# Sheet1.net
KiCad netlist of a schematic drawn in Altium Designer
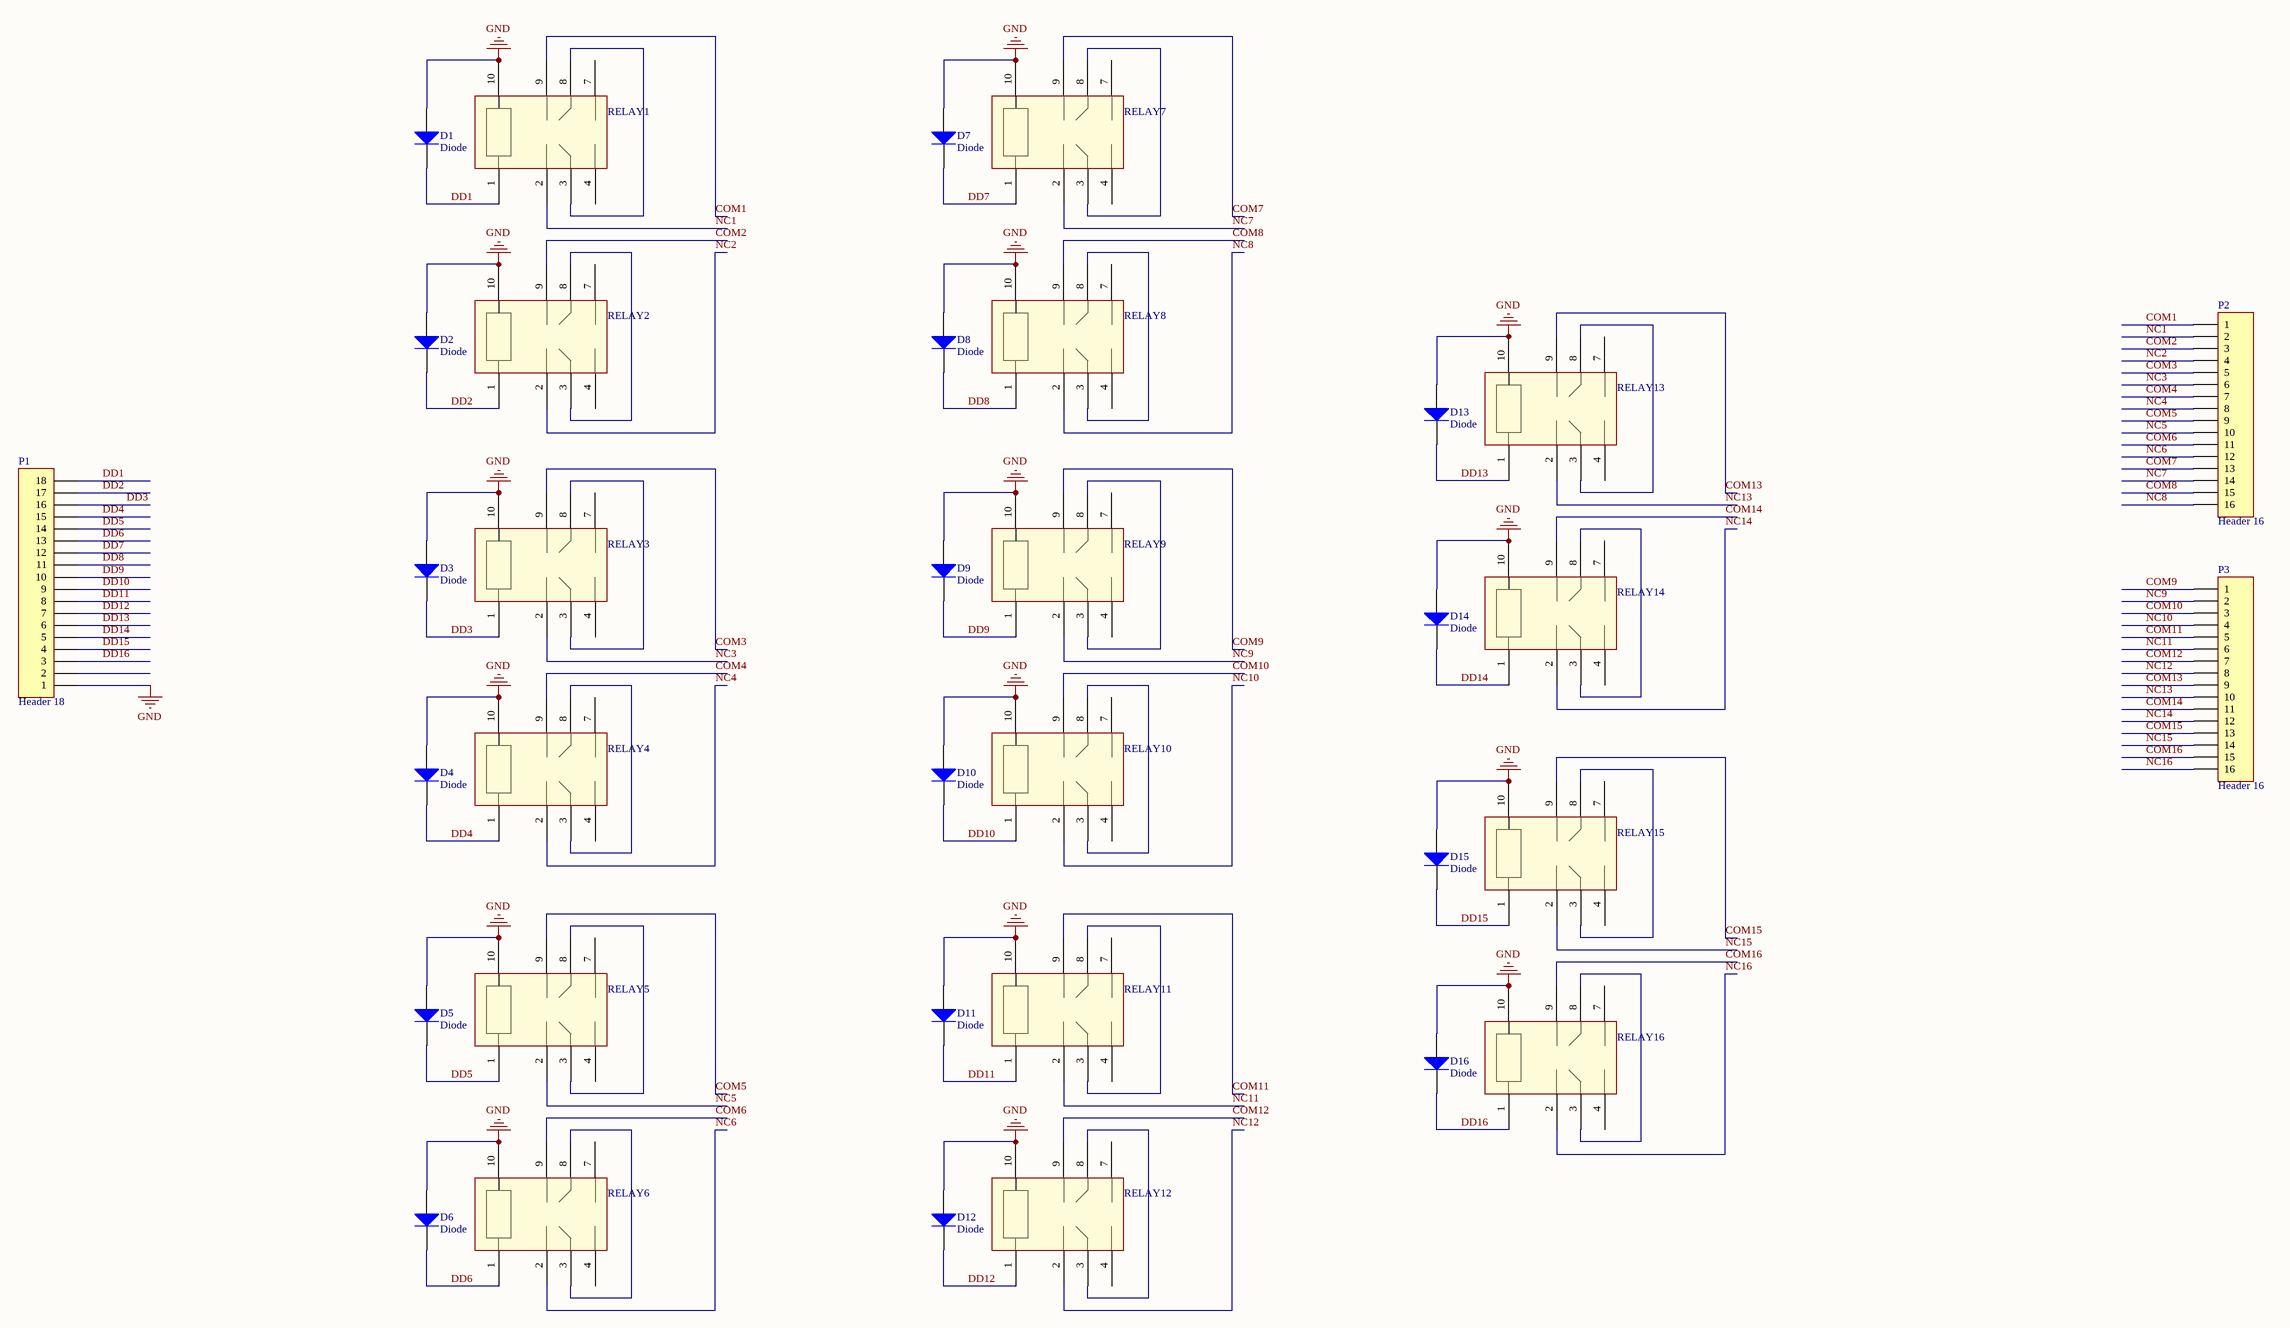
[diagram p0: Sheet1.SchDoc]

(export (version "E")
  (design (tool "Eeschema 10.0.6"))
  (components
    (comp (ref "D1")
      (value "Diode")
      (footprint "SMC")
      (description "Default Diode")
      (fields (field (name "PUBLISHER") "Altium Limited"))
      (libsource (lib "Miscellaneous Devices") (part "Diode"))
    )
    (comp (ref "D2")
      (value "Diode")
      (footprint "SMC")
      (description "Default Diode")
      (fields (field (name "PUBLISHER") "Altium Limited"))
      (libsource (lib "Miscellaneous Devices") (part "Diode"))
    )
    (comp (ref "D3")
      (value "Diode")
      (footprint "SMC")
      (description "Default Diode")
      (fields (field (name "PUBLISHER") "Altium Limited"))
      (libsource (lib "Miscellaneous Devices") (part "Diode"))
    )
    (comp (ref "D4")
      (value "Diode")
      (footprint "SMC")
      (description "Default Diode")
      (fields (field (name "PUBLISHER") "Altium Limited"))
      (libsource (lib "Miscellaneous Devices") (part "Diode"))
    )
    (comp (ref "D5")
      (value "Diode")
      (footprint "SMC")
      (description "Default Diode")
      (fields (field (name "PUBLISHER") "Altium Limited"))
      (libsource (lib "Miscellaneous Devices") (part "Diode"))
    )
    (comp (ref "D6")
      (value "Diode")
      (footprint "SMC")
      (description "Default Diode")
      (fields (field (name "PUBLISHER") "Altium Limited"))
      (libsource (lib "Miscellaneous Devices") (part "Diode"))
    )
    (comp (ref "D7")
      (value "Diode")
      (footprint "SMC")
      (description "Default Diode")
      (fields (field (name "PUBLISHER") "Altium Limited"))
      (libsource (lib "Miscellaneous Devices") (part "Diode"))
    )
    (comp (ref "D8")
      (value "Diode")
      (footprint "SMC")
      (description "Default Diode")
      (fields (field (name "PUBLISHER") "Altium Limited"))
      (libsource (lib "Miscellaneous Devices") (part "Diode"))
    )
    (comp (ref "D9")
      (value "Diode")
      (footprint "SMC")
      (description "Default Diode")
      (fields (field (name "PUBLISHER") "Altium Limited"))
      (libsource (lib "Miscellaneous Devices") (part "Diode"))
    )
    (comp (ref "D10")
      (value "Diode")
      (footprint "SMC")
      (description "Default Diode")
      (fields (field (name "PUBLISHER") "Altium Limited"))
      (libsource (lib "Miscellaneous Devices") (part "Diode"))
    )
    (comp (ref "D11")
      (value "Diode")
      (footprint "SMC")
      (description "Default Diode")
      (fields (field (name "PUBLISHER") "Altium Limited"))
      (libsource (lib "Miscellaneous Devices") (part "Diode"))
    )
    (comp (ref "D12")
      (value "Diode")
      (footprint "SMC")
      (description "Default Diode")
      (fields (field (name "PUBLISHER") "Altium Limited"))
      (libsource (lib "Miscellaneous Devices") (part "Diode"))
    )
    (comp (ref "D13")
      (value "Diode")
      (footprint "SMC")
      (description "Default Diode")
      (fields (field (name "PUBLISHER") "Altium Limited"))
      (libsource (lib "Miscellaneous Devices") (part "Diode"))
    )
    (comp (ref "D14")
      (value "Diode")
      (footprint "SMC")
      (description "Default Diode")
      (fields (field (name "PUBLISHER") "Altium Limited"))
      (libsource (lib "Miscellaneous Devices") (part "Diode"))
    )
    (comp (ref "D15")
      (value "Diode")
      (footprint "SMC")
      (description "Default Diode")
      (fields (field (name "PUBLISHER") "Altium Limited"))
      (libsource (lib "Miscellaneous Devices") (part "Diode"))
    )
    (comp (ref "D16")
      (value "Diode")
      (footprint "SMC")
      (description "Default Diode")
      (fields (field (name "PUBLISHER") "Altium Limited"))
      (libsource (lib "Miscellaneous Devices") (part "Diode"))
    )
    (comp (ref "P1")
      (value "Header 18")
      (footprint "CON 18")
      (description "Header, 18-Pin")
      (fields (field (name "PUBLISHER") "Altium Limited"))
      (libsource (lib "Miscellaneous Connectors") (part "Header 18"))
    )
    (comp (ref "P2")
      (value "Header 16")
      (footprint "CON 16")
      (description "Header, 16-Pin")
      (fields (field (name "PUBLISHER") "Altium Limited"))
      (libsource (lib "Miscellaneous Connectors") (part "Header 16"))
    )
    (comp (ref "P3")
      (value "Header 16")
      (footprint "CON 16")
      (description "Header, 16-Pin")
      (fields (field (name "PUBLISHER") "Altium Limited"))
      (libsource (lib "Miscellaneous Connectors") (part "Header 16"))
    )
    (comp (ref "RELAY1")
      (value "OMRON RELAY")
      (footprint "G6H-2")
      (libsource (lib "dung_maker_2018") (part "OMRON G6H-2"))
    )
    (comp (ref "RELAY2")
      (value "OMRON RELAY")
      (footprint "G6H-2")
      (libsource (lib "dung_maker_2018") (part "OMRON G6H-2"))
    )
    (comp (ref "RELAY3")
      (value "OMRON RELAY")
      (footprint "G6H-2")
      (libsource (lib "dung_maker_2018") (part "OMRON G6H-2"))
    )
    (comp (ref "RELAY4")
      (value "OMRON RELAY")
      (footprint "G6H-2")
      (libsource (lib "dung_maker_2018") (part "OMRON G6H-2"))
    )
    (comp (ref "RELAY5")
      (value "OMRON RELAY")
      (footprint "G6H-2")
      (libsource (lib "dung_maker_2018") (part "OMRON G6H-2"))
    )
    (comp (ref "RELAY6")
      (value "OMRON RELAY")
      (footprint "G6H-2")
      (libsource (lib "dung_maker_2018") (part "OMRON G6H-2"))
    )
    (comp (ref "RELAY7")
      (value "OMRON RELAY")
      (footprint "G6H-2")
      (libsource (lib "dung_maker_2018") (part "OMRON G6H-2"))
    )
    (comp (ref "RELAY8")
      (value "OMRON RELAY")
      (footprint "G6H-2")
      (libsource (lib "dung_maker_2018") (part "OMRON G6H-2"))
    )
    (comp (ref "RELAY9")
      (value "OMRON RELAY")
      (footprint "G6H-2")
      (libsource (lib "dung_maker_2018") (part "OMRON G6H-2"))
    )
    (comp (ref "RELAY10")
      (value "OMRON RELAY")
      (footprint "G6H-2")
      (libsource (lib "dung_maker_2018") (part "OMRON G6H-2"))
    )
    (comp (ref "RELAY11")
      (value "OMRON RELAY")
      (footprint "G6H-2")
      (libsource (lib "dung_maker_2018") (part "OMRON G6H-2"))
    )
    (comp (ref "RELAY12")
      (value "OMRON RELAY")
      (footprint "G6H-2")
      (libsource (lib "dung_maker_2018") (part "OMRON G6H-2"))
    )
    (comp (ref "RELAY13")
      (value "OMRON RELAY")
      (footprint "G6H-2")
      (libsource (lib "dung_maker_2018") (part "OMRON G6H-2"))
    )
    (comp (ref "RELAY14")
      (value "OMRON RELAY")
      (footprint "G6H-2")
      (libsource (lib "dung_maker_2018") (part "OMRON G6H-2"))
    )
    (comp (ref "RELAY15")
      (value "OMRON RELAY")
      (footprint "G6H-2")
      (libsource (lib "dung_maker_2018") (part "OMRON G6H-2"))
    )
    (comp (ref "RELAY16")
      (value "OMRON RELAY")
      (footprint "G6H-2")
      (libsource (lib "dung_maker_2018") (part "OMRON G6H-2"))
    )
  )
  (nets
    (net (code "1") (name "/COM1") (class "Default")
      (node (ref "P2") (pin "1") (pinfunction "1_1") (pintype "passive"))
      (node (ref "RELAY1") (pin "9") (pinfunction "9_9") (pintype "passive"))
    )
    (net (code "2") (name "/COM2") (class "Default")
      (node (ref "P2") (pin "3") (pinfunction "3_3") (pintype "passive"))
      (node (ref "RELAY2") (pin "9") (pinfunction "9_9") (pintype "passive"))
    )
    (net (code "3") (name "/COM3") (class "Default")
      (node (ref "P2") (pin "5") (pinfunction "5_5") (pintype "passive"))
      (node (ref "RELAY3") (pin "9") (pinfunction "9_9") (pintype "passive"))
    )
    (net (code "4") (name "/COM4") (class "Default")
      (node (ref "P2") (pin "7") (pinfunction "7_7") (pintype "passive"))
      (node (ref "RELAY4") (pin "9") (pinfunction "9_9") (pintype "passive"))
    )
    (net (code "5") (name "/COM5") (class "Default")
      (node (ref "P2") (pin "9") (pinfunction "9_9") (pintype "passive"))
      (node (ref "RELAY5") (pin "9") (pinfunction "9_9") (pintype "passive"))
    )
    (net (code "6") (name "/COM6") (class "Default")
      (node (ref "P2") (pin "11") (pinfunction "11_11") (pintype "passive"))
      (node (ref "RELAY6") (pin "9") (pinfunction "9_9") (pintype "passive"))
    )
    (net (code "7") (name "/COM7") (class "Default")
      (node (ref "P2") (pin "13") (pinfunction "13_13") (pintype "passive"))
      (node (ref "RELAY7") (pin "9") (pinfunction "9_9") (pintype "passive"))
    )
    (net (code "8") (name "/COM8") (class "Default")
      (node (ref "P2") (pin "15") (pinfunction "15_15") (pintype "passive"))
      (node (ref "RELAY8") (pin "9") (pinfunction "9_9") (pintype "passive"))
    )
    (net (code "9") (name "/COM9") (class "Default")
      (node (ref "P3") (pin "1") (pinfunction "1_1") (pintype "passive"))
      (node (ref "RELAY9") (pin "9") (pinfunction "9_9") (pintype "passive"))
    )
    (net (code "10") (name "/COM10") (class "Default")
      (node (ref "P3") (pin "3") (pinfunction "3_3") (pintype "passive"))
      (node (ref "RELAY10") (pin "9") (pinfunction "9_9") (pintype "passive"))
    )
    (net (code "11") (name "/COM11") (class "Default")
      (node (ref "P3") (pin "5") (pinfunction "5_5") (pintype "passive"))
      (node (ref "RELAY11") (pin "9") (pinfunction "9_9") (pintype "passive"))
    )
    (net (code "12") (name "/COM12") (class "Default")
      (node (ref "P3") (pin "7") (pinfunction "7_7") (pintype "passive"))
      (node (ref "RELAY12") (pin "9") (pinfunction "9_9") (pintype "passive"))
    )
    (net (code "13") (name "/COM13") (class "Default")
      (node (ref "P3") (pin "9") (pinfunction "9_9") (pintype "passive"))
      (node (ref "RELAY13") (pin "9") (pinfunction "9_9") (pintype "passive"))
    )
    (net (code "14") (name "/COM14") (class "Default")
      (node (ref "P3") (pin "11") (pinfunction "11_11") (pintype "passive"))
      (node (ref "RELAY14") (pin "9") (pinfunction "9_9") (pintype "passive"))
    )
    (net (code "15") (name "/COM15") (class "Default")
      (node (ref "P3") (pin "13") (pinfunction "13_13") (pintype "passive"))
      (node (ref "RELAY15") (pin "9") (pinfunction "9_9") (pintype "passive"))
    )
    (net (code "16") (name "/COM16") (class "Default")
      (node (ref "P3") (pin "15") (pinfunction "15_15") (pintype "passive"))
      (node (ref "RELAY16") (pin "9") (pinfunction "9_9") (pintype "passive"))
    )
    (net (code "17") (name "/DD1") (class "Default")
      (node (ref "D1") (pin "2") (pinfunction "K_2") (pintype "passive"))
      (node (ref "P1") (pin "18") (pinfunction "18_18") (pintype "passive"))
      (node (ref "RELAY1") (pin "1") (pinfunction "1_1") (pintype "passive"))
    )
    (net (code "18") (name "/DD2") (class "Default")
      (node (ref "D2") (pin "2") (pinfunction "K_2") (pintype "passive"))
      (node (ref "P1") (pin "17") (pinfunction "17_17") (pintype "passive"))
      (node (ref "RELAY2") (pin "1") (pinfunction "1_1") (pintype "passive"))
    )
    (net (code "19") (name "/DD3") (class "Default")
      (node (ref "D3") (pin "2") (pinfunction "K_2") (pintype "passive"))
      (node (ref "P1") (pin "16") (pinfunction "16_16") (pintype "passive"))
      (node (ref "RELAY3") (pin "1") (pinfunction "1_1") (pintype "passive"))
    )
    (net (code "20") (name "/DD4") (class "Default")
      (node (ref "D4") (pin "2") (pinfunction "K_2") (pintype "passive"))
      (node (ref "P1") (pin "15") (pinfunction "15_15") (pintype "passive"))
      (node (ref "RELAY4") (pin "1") (pinfunction "1_1") (pintype "passive"))
    )
    (net (code "21") (name "/DD5") (class "Default")
      (node (ref "D5") (pin "2") (pinfunction "K_2") (pintype "passive"))
      (node (ref "P1") (pin "14") (pinfunction "14_14") (pintype "passive"))
      (node (ref "RELAY5") (pin "1") (pinfunction "1_1") (pintype "passive"))
    )
    (net (code "22") (name "/DD6") (class "Default")
      (node (ref "D6") (pin "2") (pinfunction "K_2") (pintype "passive"))
      (node (ref "P1") (pin "13") (pinfunction "13_13") (pintype "passive"))
      (node (ref "RELAY6") (pin "1") (pinfunction "1_1") (pintype "passive"))
    )
    (net (code "23") (name "/DD7") (class "Default")
      (node (ref "D7") (pin "2") (pinfunction "K_2") (pintype "passive"))
      (node (ref "P1") (pin "12") (pinfunction "12_12") (pintype "passive"))
      (node (ref "RELAY7") (pin "1") (pinfunction "1_1") (pintype "passive"))
    )
    (net (code "24") (name "/DD8") (class "Default")
      (node (ref "D8") (pin "2") (pinfunction "K_2") (pintype "passive"))
      (node (ref "P1") (pin "11") (pinfunction "11_11") (pintype "passive"))
      (node (ref "RELAY8") (pin "1") (pinfunction "1_1") (pintype "passive"))
    )
    (net (code "25") (name "/DD9") (class "Default")
      (node (ref "D9") (pin "2") (pinfunction "K_2") (pintype "passive"))
      (node (ref "P1") (pin "10") (pinfunction "10_10") (pintype "passive"))
      (node (ref "RELAY9") (pin "1") (pinfunction "1_1") (pintype "passive"))
    )
    (net (code "26") (name "/DD10") (class "Default")
      (node (ref "D10") (pin "2") (pinfunction "K_2") (pintype "passive"))
      (node (ref "P1") (pin "9") (pinfunction "9_9") (pintype "passive"))
      (node (ref "RELAY10") (pin "1") (pinfunction "1_1") (pintype "passive"))
    )
    (net (code "27") (name "/DD11") (class "Default")
      (node (ref "D11") (pin "2") (pinfunction "K_2") (pintype "passive"))
      (node (ref "P1") (pin "8") (pinfunction "8_8") (pintype "passive"))
      (node (ref "RELAY11") (pin "1") (pinfunction "1_1") (pintype "passive"))
    )
    (net (code "28") (name "/DD12") (class "Default")
      (node (ref "D12") (pin "2") (pinfunction "K_2") (pintype "passive"))
      (node (ref "P1") (pin "7") (pinfunction "7_7") (pintype "passive"))
      (node (ref "RELAY12") (pin "1") (pinfunction "1_1") (pintype "passive"))
    )
    (net (code "29") (name "/DD13") (class "Default")
      (node (ref "D13") (pin "2") (pinfunction "K_2") (pintype "passive"))
      (node (ref "P1") (pin "6") (pinfunction "6_6") (pintype "passive"))
      (node (ref "RELAY13") (pin "1") (pinfunction "1_1") (pintype "passive"))
    )
    (net (code "30") (name "/DD14") (class "Default")
      (node (ref "D14") (pin "2") (pinfunction "K_2") (pintype "passive"))
      (node (ref "P1") (pin "5") (pinfunction "5_5") (pintype "passive"))
      (node (ref "RELAY14") (pin "1") (pinfunction "1_1") (pintype "passive"))
    )
    (net (code "31") (name "/DD15") (class "Default")
      (node (ref "D15") (pin "2") (pinfunction "K_2") (pintype "passive"))
      (node (ref "P1") (pin "4") (pinfunction "4_4") (pintype "passive"))
      (node (ref "RELAY15") (pin "1") (pinfunction "1_1") (pintype "passive"))
    )
    (net (code "32") (name "/DD16") (class "Default")
      (node (ref "D16") (pin "2") (pinfunction "K_2") (pintype "passive"))
      (node (ref "P1") (pin "3") (pinfunction "3_3") (pintype "passive"))
      (node (ref "RELAY16") (pin "1") (pinfunction "1_1") (pintype "passive"))
    )
    (net (code "33") (name "/NC1") (class "Default")
      (node (ref "P2") (pin "2") (pinfunction "2_2") (pintype "passive"))
      (node (ref "RELAY1") (pin "2") (pinfunction "2_2") (pintype "passive"))
    )
    (net (code "34") (name "/NC2") (class "Default")
      (node (ref "P2") (pin "4") (pinfunction "4_4") (pintype "passive"))
      (node (ref "RELAY2") (pin "2") (pinfunction "2_2") (pintype "passive"))
    )
    (net (code "35") (name "/NC3") (class "Default")
      (node (ref "P2") (pin "6") (pinfunction "6_6") (pintype "passive"))
      (node (ref "RELAY3") (pin "2") (pinfunction "2_2") (pintype "passive"))
    )
    (net (code "36") (name "/NC4") (class "Default")
      (node (ref "P2") (pin "8") (pinfunction "8_8") (pintype "passive"))
      (node (ref "RELAY4") (pin "2") (pinfunction "2_2") (pintype "passive"))
    )
    (net (code "37") (name "/NC5") (class "Default")
      (node (ref "P2") (pin "10") (pinfunction "10_10") (pintype "passive"))
      (node (ref "RELAY5") (pin "2") (pinfunction "2_2") (pintype "passive"))
    )
    (net (code "38") (name "/NC6") (class "Default")
      (node (ref "P2") (pin "12") (pinfunction "12_12") (pintype "passive"))
      (node (ref "RELAY6") (pin "2") (pinfunction "2_2") (pintype "passive"))
    )
    (net (code "39") (name "/NC7") (class "Default")
      (node (ref "P2") (pin "14") (pinfunction "14_14") (pintype "passive"))
      (node (ref "RELAY7") (pin "2") (pinfunction "2_2") (pintype "passive"))
    )
    (net (code "40") (name "/NC8") (class "Default")
      (node (ref "P2") (pin "16") (pinfunction "16_16") (pintype "passive"))
      (node (ref "RELAY8") (pin "2") (pinfunction "2_2") (pintype "passive"))
    )
    (net (code "41") (name "/NC9") (class "Default")
      (node (ref "P3") (pin "2") (pinfunction "2_2") (pintype "passive"))
      (node (ref "RELAY9") (pin "2") (pinfunction "2_2") (pintype "passive"))
    )
    (net (code "42") (name "/NC10") (class "Default")
      (node (ref "P3") (pin "4") (pinfunction "4_4") (pintype "passive"))
      (node (ref "RELAY10") (pin "2") (pinfunction "2_2") (pintype "passive"))
    )
    (net (code "43") (name "/NC11") (class "Default")
      (node (ref "P3") (pin "6") (pinfunction "6_6") (pintype "passive"))
      (node (ref "RELAY11") (pin "2") (pinfunction "2_2") (pintype "passive"))
    )
    (net (code "44") (name "/NC12") (class "Default")
      (node (ref "P3") (pin "8") (pinfunction "8_8") (pintype "passive"))
      (node (ref "RELAY12") (pin "2") (pinfunction "2_2") (pintype "passive"))
    )
    (net (code "45") (name "/NC13") (class "Default")
      (node (ref "P3") (pin "10") (pinfunction "10_10") (pintype "passive"))
      (node (ref "RELAY13") (pin "2") (pinfunction "2_2") (pintype "passive"))
    )
    (net (code "46") (name "/NC14") (class "Default")
      (node (ref "P3") (pin "12") (pinfunction "12_12") (pintype "passive"))
      (node (ref "RELAY14") (pin "2") (pinfunction "2_2") (pintype "passive"))
    )
    (net (code "47") (name "/NC15") (class "Default")
      (node (ref "P3") (pin "14") (pinfunction "14_14") (pintype "passive"))
      (node (ref "RELAY15") (pin "2") (pinfunction "2_2") (pintype "passive"))
    )
    (net (code "48") (name "/NC16") (class "Default")
      (node (ref "P3") (pin "16") (pinfunction "16_16") (pintype "passive"))
      (node (ref "RELAY16") (pin "2") (pinfunction "2_2") (pintype "passive"))
    )
    (net (code "49") (name "GND") (class "Default")
      (node (ref "D1") (pin "1") (pinfunction "A_1") (pintype "passive"))
      (node (ref "D10") (pin "1") (pinfunction "A_1") (pintype "passive"))
      (node (ref "D11") (pin "1") (pinfunction "A_1") (pintype "passive"))
      (node (ref "D12") (pin "1") (pinfunction "A_1") (pintype "passive"))
      (node (ref "D13") (pin "1") (pinfunction "A_1") (pintype "passive"))
      (node (ref "D14") (pin "1") (pinfunction "A_1") (pintype "passive"))
      (node (ref "D15") (pin "1") (pinfunction "A_1") (pintype "passive"))
      (node (ref "D16") (pin "1") (pinfunction "A_1") (pintype "passive"))
      (node (ref "D2") (pin "1") (pinfunction "A_1") (pintype "passive"))
      (node (ref "D3") (pin "1") (pinfunction "A_1") (pintype "passive"))
      (node (ref "D4") (pin "1") (pinfunction "A_1") (pintype "passive"))
      (node (ref "D5") (pin "1") (pinfunction "A_1") (pintype "passive"))
      (node (ref "D6") (pin "1") (pinfunction "A_1") (pintype "passive"))
      (node (ref "D7") (pin "1") (pinfunction "A_1") (pintype "passive"))
      (node (ref "D8") (pin "1") (pinfunction "A_1") (pintype "passive"))
      (node (ref "D9") (pin "1") (pinfunction "A_1") (pintype "passive"))
      (node (ref "P1") (pin "1") (pinfunction "1_1") (pintype "passive"))
      (node (ref "RELAY1") (pin "10") (pinfunction "10_10") (pintype "passive"))
      (node (ref "RELAY10") (pin "10") (pinfunction "10_10") (pintype "passive"))
      (node (ref "RELAY11") (pin "10") (pinfunction "10_10") (pintype "passive"))
      (node (ref "RELAY12") (pin "10") (pinfunction "10_10") (pintype "passive"))
      (node (ref "RELAY13") (pin "10") (pinfunction "10_10") (pintype "passive"))
      (node (ref "RELAY14") (pin "10") (pinfunction "10_10") (pintype "passive"))
      (node (ref "RELAY15") (pin "10") (pinfunction "10_10") (pintype "passive"))
      (node (ref "RELAY16") (pin "10") (pinfunction "10_10") (pintype "passive"))
      (node (ref "RELAY2") (pin "10") (pinfunction "10_10") (pintype "passive"))
      (node (ref "RELAY3") (pin "10") (pinfunction "10_10") (pintype "passive"))
      (node (ref "RELAY4") (pin "10") (pinfunction "10_10") (pintype "passive"))
      (node (ref "RELAY5") (pin "10") (pinfunction "10_10") (pintype "passive"))
      (node (ref "RELAY6") (pin "10") (pinfunction "10_10") (pintype "passive"))
      (node (ref "RELAY7") (pin "10") (pinfunction "10_10") (pintype "passive"))
      (node (ref "RELAY8") (pin "10") (pinfunction "10_10") (pintype "passive"))
      (node (ref "RELAY9") (pin "10") (pinfunction "10_10") (pintype "passive"))
    )
    (net (code "50") (name "Net-(RELAY1-Pad3)") (class "Default")
      (node (ref "RELAY1") (pin "3") (pinfunction "3_3") (pintype "passive"))
      (node (ref "RELAY1") (pin "8") (pinfunction "8_8") (pintype "passive"))
    )
    (net (code "51") (name "Net-(RELAY2-Pad3)") (class "Default")
      (node (ref "RELAY2") (pin "3") (pinfunction "3_3") (pintype "passive"))
      (node (ref "RELAY2") (pin "8") (pinfunction "8_8") (pintype "passive"))
    )
    (net (code "52") (name "Net-(RELAY3-Pad3)") (class "Default")
      (node (ref "RELAY3") (pin "3") (pinfunction "3_3") (pintype "passive"))
      (node (ref "RELAY3") (pin "8") (pinfunction "8_8") (pintype "passive"))
    )
    (net (code "53") (name "Net-(RELAY4-Pad3)") (class "Default")
      (node (ref "RELAY4") (pin "3") (pinfunction "3_3") (pintype "passive"))
      (node (ref "RELAY4") (pin "8") (pinfunction "8_8") (pintype "passive"))
    )
    (net (code "54") (name "Net-(RELAY5-Pad3)") (class "Default")
      (node (ref "RELAY5") (pin "3") (pinfunction "3_3") (pintype "passive"))
      (node (ref "RELAY5") (pin "8") (pinfunction "8_8") (pintype "passive"))
    )
    (net (code "55") (name "Net-(RELAY6-Pad3)") (class "Default")
      (node (ref "RELAY6") (pin "3") (pinfunction "3_3") (pintype "passive"))
      (node (ref "RELAY6") (pin "8") (pinfunction "8_8") (pintype "passive"))
    )
    (net (code "56") (name "Net-(RELAY7-Pad3)") (class "Default")
      (node (ref "RELAY7") (pin "3") (pinfunction "3_3") (pintype "passive"))
      (node (ref "RELAY7") (pin "8") (pinfunction "8_8") (pintype "passive"))
    )
    (net (code "57") (name "Net-(RELAY8-Pad3)") (class "Default")
      (node (ref "RELAY8") (pin "3") (pinfunction "3_3") (pintype "passive"))
      (node (ref "RELAY8") (pin "8") (pinfunction "8_8") (pintype "passive"))
    )
    (net (code "58") (name "Net-(RELAY9-Pad3)") (class "Default")
      (node (ref "RELAY9") (pin "3") (pinfunction "3_3") (pintype "passive"))
      (node (ref "RELAY9") (pin "8") (pinfunction "8_8") (pintype "passive"))
    )
    (net (code "59") (name "Net-(RELAY10-Pad3)") (class "Default")
      (node (ref "RELAY10") (pin "3") (pinfunction "3_3") (pintype "passive"))
      (node (ref "RELAY10") (pin "8") (pinfunction "8_8") (pintype "passive"))
    )
    (net (code "60") (name "Net-(RELAY11-Pad3)") (class "Default")
      (node (ref "RELAY11") (pin "3") (pinfunction "3_3") (pintype "passive"))
      (node (ref "RELAY11") (pin "8") (pinfunction "8_8") (pintype "passive"))
    )
    (net (code "61") (name "Net-(RELAY12-Pad3)") (class "Default")
      (node (ref "RELAY12") (pin "3") (pinfunction "3_3") (pintype "passive"))
      (node (ref "RELAY12") (pin "8") (pinfunction "8_8") (pintype "passive"))
    )
    (net (code "62") (name "Net-(RELAY13-Pad3)") (class "Default")
      (node (ref "RELAY13") (pin "3") (pinfunction "3_3") (pintype "passive"))
      (node (ref "RELAY13") (pin "8") (pinfunction "8_8") (pintype "passive"))
    )
    (net (code "63") (name "Net-(RELAY14-Pad3)") (class "Default")
      (node (ref "RELAY14") (pin "3") (pinfunction "3_3") (pintype "passive"))
      (node (ref "RELAY14") (pin "8") (pinfunction "8_8") (pintype "passive"))
    )
    (net (code "64") (name "Net-(RELAY15-Pad3)") (class "Default")
      (node (ref "RELAY15") (pin "3") (pinfunction "3_3") (pintype "passive"))
      (node (ref "RELAY15") (pin "8") (pinfunction "8_8") (pintype "passive"))
    )
    (net (code "65") (name "Net-(RELAY16-Pad3)") (class "Default")
      (node (ref "RELAY16") (pin "3") (pinfunction "3_3") (pintype "passive"))
      (node (ref "RELAY16") (pin "8") (pinfunction "8_8") (pintype "passive"))
    )
    (net (code "66") (name "unconnected-(P1-Pad2)") (class "Default")
      (node (ref "P1") (pin "2") (pinfunction "2_2") (pintype "passive"))
    )
    (net (code "67") (name "unconnected-(RELAY1-Pad4)") (class "Default")
      (node (ref "RELAY1") (pin "4") (pinfunction "4_4") (pintype "passive"))
    )
    (net (code "68") (name "unconnected-(RELAY1-Pad5)") (class "Default")
      (node (ref "RELAY1") (pin "5") (pinfunction "5_5") (pintype "passive"))
    )
    (net (code "69") (name "unconnected-(RELAY1-Pad6)") (class "Default")
      (node (ref "RELAY1") (pin "6") (pinfunction "6_6") (pintype "passive"))
    )
    (net (code "70") (name "unconnected-(RELAY1-Pad7)") (class "Default")
      (node (ref "RELAY1") (pin "7") (pinfunction "7_7") (pintype "passive"))
    )
    (net (code "71") (name "unconnected-(RELAY2-Pad4)") (class "Default")
      (node (ref "RELAY2") (pin "4") (pinfunction "4_4") (pintype "passive"))
    )
    (net (code "72") (name "unconnected-(RELAY2-Pad5)") (class "Default")
      (node (ref "RELAY2") (pin "5") (pinfunction "5_5") (pintype "passive"))
    )
    (net (code "73") (name "unconnected-(RELAY2-Pad6)") (class "Default")
      (node (ref "RELAY2") (pin "6") (pinfunction "6_6") (pintype "passive"))
    )
    (net (code "74") (name "unconnected-(RELAY2-Pad7)") (class "Default")
      (node (ref "RELAY2") (pin "7") (pinfunction "7_7") (pintype "passive"))
    )
    (net (code "75") (name "unconnected-(RELAY3-Pad4)") (class "Default")
      (node (ref "RELAY3") (pin "4") (pinfunction "4_4") (pintype "passive"))
    )
    (net (code "76") (name "unconnected-(RELAY3-Pad5)") (class "Default")
      (node (ref "RELAY3") (pin "5") (pinfunction "5_5") (pintype "passive"))
    )
    (net (code "77") (name "unconnected-(RELAY3-Pad6)") (class "Default")
      (node (ref "RELAY3") (pin "6") (pinfunction "6_6") (pintype "passive"))
    )
    (net (code "78") (name "unconnected-(RELAY3-Pad7)") (class "Default")
      (node (ref "RELAY3") (pin "7") (pinfunction "7_7") (pintype "passive"))
    )
    (net (code "79") (name "unconnected-(RELAY4-Pad4)") (class "Default")
      (node (ref "RELAY4") (pin "4") (pinfunction "4_4") (pintype "passive"))
    )
    (net (code "80") (name "unconnected-(RELAY4-Pad5)") (class "Default")
      (node (ref "RELAY4") (pin "5") (pinfunction "5_5") (pintype "passive"))
    )
    (net (code "81") (name "unconnected-(RELAY4-Pad6)") (class "Default")
      (node (ref "RELAY4") (pin "6") (pinfunction "6_6") (pintype "passive"))
    )
    (net (code "82") (name "unconnected-(RELAY4-Pad7)") (class "Default")
      (node (ref "RELAY4") (pin "7") (pinfunction "7_7") (pintype "passive"))
    )
    (net (code "83") (name "unconnected-(RELAY5-Pad4)") (class "Default")
      (node (ref "RELAY5") (pin "4") (pinfunction "4_4") (pintype "passive"))
    )
    (net (code "84") (name "unconnected-(RELAY5-Pad5)") (class "Default")
      (node (ref "RELAY5") (pin "5") (pinfunction "5_5") (pintype "passive"))
    )
    (net (code "85") (name "unconnected-(RELAY5-Pad6)") (class "Default")
      (node (ref "RELAY5") (pin "6") (pinfunction "6_6") (pintype "passive"))
    )
    (net (code "86") (name "unconnected-(RELAY5-Pad7)") (class "Default")
      (node (ref "RELAY5") (pin "7") (pinfunction "7_7") (pintype "passive"))
    )
    (net (code "87") (name "unconnected-(RELAY6-Pad4)") (class "Default")
      (node (ref "RELAY6") (pin "4") (pinfunction "4_4") (pintype "passive"))
    )
    (net (code "88") (name "unconnected-(RELAY6-Pad5)") (class "Default")
      (node (ref "RELAY6") (pin "5") (pinfunction "5_5") (pintype "passive"))
    )
    (net (code "89") (name "unconnected-(RELAY6-Pad6)") (class "Default")
      (node (ref "RELAY6") (pin "6") (pinfunction "6_6") (pintype "passive"))
    )
    (net (code "90") (name "unconnected-(RELAY6-Pad7)") (class "Default")
      (node (ref "RELAY6") (pin "7") (pinfunction "7_7") (pintype "passive"))
    )
    (net (code "91") (name "unconnected-(RELAY7-Pad4)") (class "Default")
      (node (ref "RELAY7") (pin "4") (pinfunction "4_4") (pintype "passive"))
    )
    (net (code "92") (name "unconnected-(RELAY7-Pad5)") (class "Default")
      (node (ref "RELAY7") (pin "5") (pinfunction "5_5") (pintype "passive"))
    )
    (net (code "93") (name "unconnected-(RELAY7-Pad6)") (class "Default")
      (node (ref "RELAY7") (pin "6") (pinfunction "6_6") (pintype "passive"))
    )
    (net (code "94") (name "unconnected-(RELAY7-Pad7)") (class "Default")
      (node (ref "RELAY7") (pin "7") (pinfunction "7_7") (pintype "passive"))
    )
    (net (code "95") (name "unconnected-(RELAY8-Pad4)") (class "Default")
      (node (ref "RELAY8") (pin "4") (pinfunction "4_4") (pintype "passive"))
    )
    (net (code "96") (name "unconnected-(RELAY8-Pad5)") (class "Default")
      (node (ref "RELAY8") (pin "5") (pinfunction "5_5") (pintype "passive"))
    )
    (net (code "97") (name "unconnected-(RELAY8-Pad6)") (class "Default")
      (node (ref "RELAY8") (pin "6") (pinfunction "6_6") (pintype "passive"))
    )
    (net (code "98") (name "unconnected-(RELAY8-Pad7)") (class "Default")
      (node (ref "RELAY8") (pin "7") (pinfunction "7_7") (pintype "passive"))
    )
    (net (code "99") (name "unconnected-(RELAY9-Pad4)") (class "Default")
      (node (ref "RELAY9") (pin "4") (pinfunction "4_4") (pintype "passive"))
    )
    (net (code "100") (name "unconnected-(RELAY9-Pad5)") (class "Default")
      (node (ref "RELAY9") (pin "5") (pinfunction "5_5") (pintype "passive"))
    )
    (net (code "101") (name "unconnected-(RELAY9-Pad6)") (class "Default")
      (node (ref "RELAY9") (pin "6") (pinfunction "6_6") (pintype "passive"))
    )
    (net (code "102") (name "unconnected-(RELAY9-Pad7)") (class "Default")
      (node (ref "RELAY9") (pin "7") (pinfunction "7_7") (pintype "passive"))
    )
    (net (code "103") (name "unconnected-(RELAY10-Pad4)") (class "Default")
      (node (ref "RELAY10") (pin "4") (pinfunction "4_4") (pintype "passive"))
    )
    (net (code "104") (name "unconnected-(RELAY10-Pad5)") (class "Default")
      (node (ref "RELAY10") (pin "5") (pinfunction "5_5") (pintype "passive"))
    )
    (net (code "105") (name "unconnected-(RELAY10-Pad6)") (class "Default")
      (node (ref "RELAY10") (pin "6") (pinfunction "6_6") (pintype "passive"))
    )
    (net (code "106") (name "unconnected-(RELAY10-Pad7)") (class "Default")
      (node (ref "RELAY10") (pin "7") (pinfunction "7_7") (pintype "passive"))
    )
    (net (code "107") (name "unconnected-(RELAY11-Pad4)") (class "Default")
      (node (ref "RELAY11") (pin "4") (pinfunction "4_4") (pintype "passive"))
    )
    (net (code "108") (name "unconnected-(RELAY11-Pad5)") (class "Default")
      (node (ref "RELAY11") (pin "5") (pinfunction "5_5") (pintype "passive"))
    )
    (net (code "109") (name "unconnected-(RELAY11-Pad6)") (class "Default")
      (node (ref "RELAY11") (pin "6") (pinfunction "6_6") (pintype "passive"))
    )
    (net (code "110") (name "unconnected-(RELAY11-Pad7)") (class "Default")
      (node (ref "RELAY11") (pin "7") (pinfunction "7_7") (pintype "passive"))
    )
    (net (code "111") (name "unconnected-(RELAY12-Pad4)") (class "Default")
      (node (ref "RELAY12") (pin "4") (pinfunction "4_4") (pintype "passive"))
    )
    (net (code "112") (name "unconnected-(RELAY12-Pad5)") (class "Default")
      (node (ref "RELAY12") (pin "5") (pinfunction "5_5") (pintype "passive"))
    )
    (net (code "113") (name "unconnected-(RELAY12-Pad6)") (class "Default")
      (node (ref "RELAY12") (pin "6") (pinfunction "6_6") (pintype "passive"))
    )
    (net (code "114") (name "unconnected-(RELAY12-Pad7)") (class "Default")
      (node (ref "RELAY12") (pin "7") (pinfunction "7_7") (pintype "passive"))
    )
    (net (code "115") (name "unconnected-(RELAY13-Pad4)") (class "Default")
      (node (ref "RELAY13") (pin "4") (pinfunction "4_4") (pintype "passive"))
    )
    (net (code "116") (name "unconnected-(RELAY13-Pad5)") (class "Default")
      (node (ref "RELAY13") (pin "5") (pinfunction "5_5") (pintype "passive"))
    )
    (net (code "117") (name "unconnected-(RELAY13-Pad6)") (class "Default")
      (node (ref "RELAY13") (pin "6") (pinfunction "6_6") (pintype "passive"))
    )
    (net (code "118") (name "unconnected-(RELAY13-Pad7)") (class "Default")
      (node (ref "RELAY13") (pin "7") (pinfunction "7_7") (pintype "passive"))
    )
    (net (code "119") (name "unconnected-(RELAY14-Pad4)") (class "Default")
      (node (ref "RELAY14") (pin "4") (pinfunction "4_4") (pintype "passive"))
    )
    (net (code "120") (name "unconnected-(RELAY14-Pad5)") (class "Default")
      (node (ref "RELAY14") (pin "5") (pinfunction "5_5") (pintype "passive"))
    )
    (net (code "121") (name "unconnected-(RELAY14-Pad6)") (class "Default")
      (node (ref "RELAY14") (pin "6") (pinfunction "6_6") (pintype "passive"))
    )
    (net (code "122") (name "unconnected-(RELAY14-Pad7)") (class "Default")
      (node (ref "RELAY14") (pin "7") (pinfunction "7_7") (pintype "passive"))
    )
    (net (code "123") (name "unconnected-(RELAY15-Pad4)") (class "Default")
      (node (ref "RELAY15") (pin "4") (pinfunction "4_4") (pintype "passive"))
    )
    (net (code "124") (name "unconnected-(RELAY15-Pad5)") (class "Default")
      (node (ref "RELAY15") (pin "5") (pinfunction "5_5") (pintype "passive"))
    )
    (net (code "125") (name "unconnected-(RELAY15-Pad6)") (class "Default")
      (node (ref "RELAY15") (pin "6") (pinfunction "6_6") (pintype "passive"))
    )
    (net (code "126") (name "unconnected-(RELAY15-Pad7)") (class "Default")
      (node (ref "RELAY15") (pin "7") (pinfunction "7_7") (pintype "passive"))
    )
    (net (code "127") (name "unconnected-(RELAY16-Pad4)") (class "Default")
      (node (ref "RELAY16") (pin "4") (pinfunction "4_4") (pintype "passive"))
    )
    (net (code "128") (name "unconnected-(RELAY16-Pad5)") (class "Default")
      (node (ref "RELAY16") (pin "5") (pinfunction "5_5") (pintype "passive"))
    )
    (net (code "129") (name "unconnected-(RELAY16-Pad6)") (class "Default")
      (node (ref "RELAY16") (pin "6") (pinfunction "6_6") (pintype "passive"))
    )
    (net (code "130") (name "unconnected-(RELAY16-Pad7)") (class "Default")
      (node (ref "RELAY16") (pin "7") (pinfunction "7_7") (pintype "passive"))
    )
  )
)
